# Gesamtschaltung.net
KiCad netlist of a schematic drawn in EAGLE
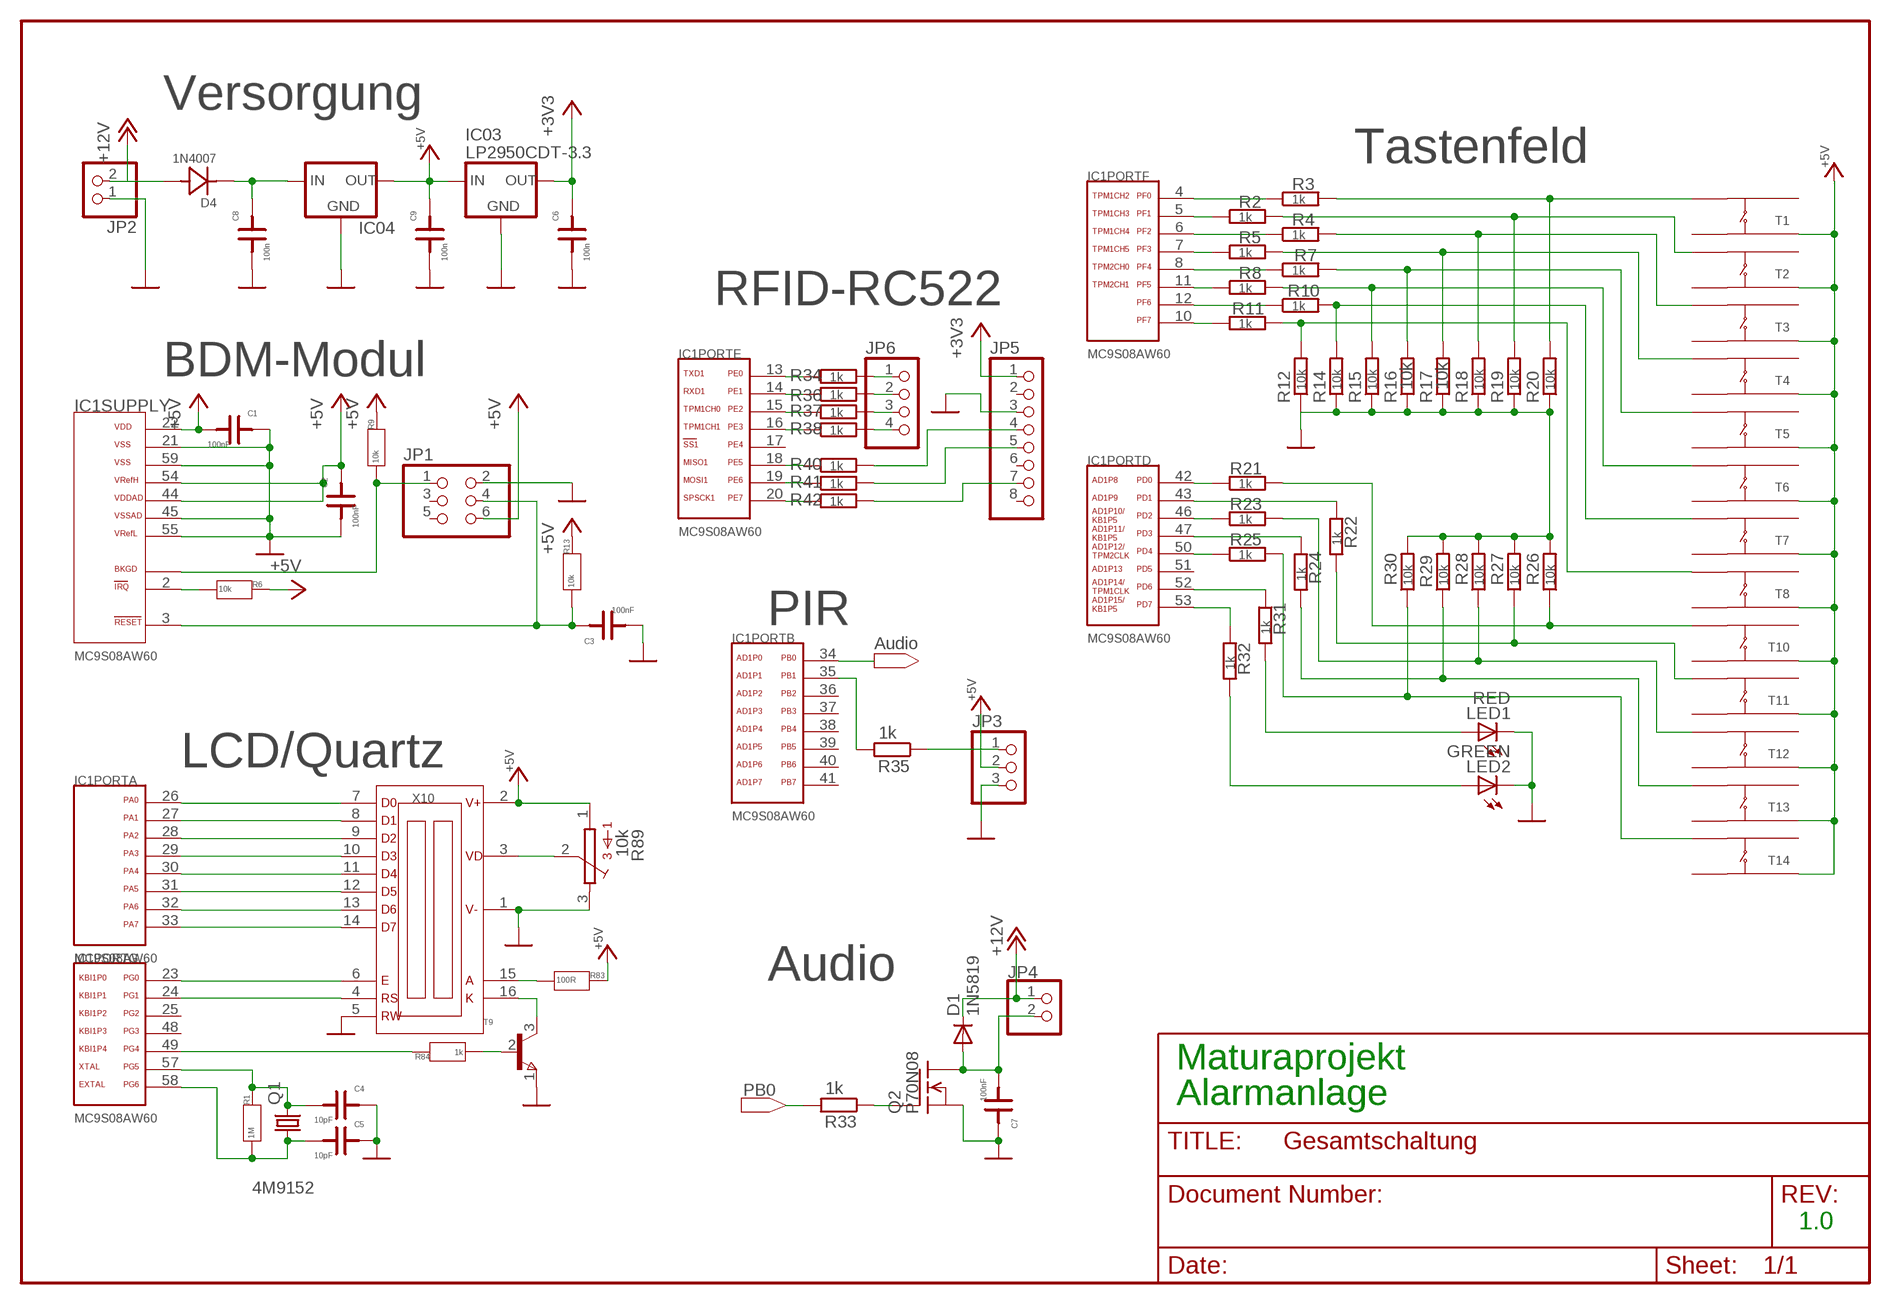
[diagram p0: schematic, sheet 1]

(export (version "E")
  (design (tool "Eeschema 10.0.6"))
  (components
    (comp (ref "C1")
      (value "100nF")
      (footprint "eagle-import:0805F")
      (libsource (lib "eagle-import") (part "C1"))
    )
    (comp (ref "C2")
      (value "100nF")
      (footprint "eagle-import:0805F")
      (libsource (lib "eagle-import") (part "C1"))
    )
    (comp (ref "C3")
      (value "100nF")
      (footprint "eagle-import:0805F")
      (libsource (lib "eagle-import") (part "C1"))
    )
    (comp (ref "C4")
      (value "10pF")
      (footprint "eagle-import:0805F")
      (libsource (lib "eagle-import") (part "C1"))
    )
    (comp (ref "C5")
      (value "10pF")
      (footprint "eagle-import:0805F")
      (libsource (lib "eagle-import") (part "C1"))
    )
    (comp (ref "C6")
      (value "100n")
      (footprint "eagle-import:0805F")
      (libsource (lib "eagle-import") (part "C1"))
    )
    (comp (ref "C7")
      (value "100nF")
      (footprint "eagle-import:0805F")
      (libsource (lib "eagle-import") (part "C1"))
    )
    (comp (ref "C8")
      (value "100n")
      (footprint "eagle-import:0805F")
      (libsource (lib "eagle-import") (part "C1"))
    )
    (comp (ref "C9")
      (value "100n")
      (footprint "eagle-import:0805F")
      (libsource (lib "eagle-import") (part "C1"))
    )
    (comp (ref "D1")
      (value "1N5819")
      (footprint "eagle-import:DO41-10")
      (libsource (lib "eagle-import") (part "1N4004"))
    )
    (comp (ref "D4")
      (value "1N4007")
      (footprint "eagle-import:D400BH")
      (libsource (lib "eagle-import") (part "DHC"))
    )
    (comp (ref "IC1")
      (value "MC9S08AW60")
      (footprint "eagle-import:LQFP64")
      (libsource (lib "eagle-import") (part "MC9S08AW60"))
    )
    (comp (ref "IC03")
      (value "LP2950CDT-3.3")
      (footprint "eagle-import:DPACK")
      (libsource (lib "eagle-import") (part "LP2950?CDT-3.3"))
    )
    (comp (ref "IC04")
      (value "78XXS")
      (footprint "eagle-import:78XXS")
      (libsource (lib "eagle-import") (part "78XXS"))
    )
    (comp (ref "JP1")
      (value "PINHD-2X3")
      (footprint "eagle-import:2X03")
      (libsource (lib "eagle-import") (part "PINHD-2X3"))
    )
    (comp (ref "JP2")
      (value "PINHD-1X2")
      (footprint "eagle-import:1X02")
      (libsource (lib "eagle-import") (part "PINHD-1X2"))
    )
    (comp (ref "JP3")
      (value "PINHD-1X3")
      (footprint "eagle-import:1X03")
      (libsource (lib "eagle-import") (part "PINHD-1X3"))
    )
    (comp (ref "JP4")
      (value "PINHD-1X2")
      (footprint "eagle-import:1X02")
      (libsource (lib "eagle-import") (part "PINHD-1X2"))
    )
    (comp (ref "JP5")
      (value "PINHD-1X8")
      (footprint "eagle-import:1X08")
      (libsource (lib "eagle-import") (part "PINHD-1X8"))
    )
    (comp (ref "JP6")
      (value "PINHD-1X4")
      (footprint "eagle-import:1X04")
      (libsource (lib "eagle-import") (part "PINHD-1X4"))
    )
    (comp (ref "LED1")
      (value "RED")
      (footprint "eagle-import:LED3MM")
      (libsource (lib "eagle-import") (part "LED3MM"))
    )
    (comp (ref "LED2")
      (value "GREEN")
      (footprint "eagle-import:LED3MM")
      (libsource (lib "eagle-import") (part "LED3MM"))
    )
    (comp (ref "Q1")
      (value "4M9152")
      (footprint "eagle-import:HC49UP")
      (libsource (lib "eagle-import") (part "HC49UP"))
    )
    (comp (ref "Q2")
      (value "P70N08")
      (footprint "eagle-import:TO220")
      (libsource (lib "eagle-import") (part "BUZ11"))
    )
    (comp (ref "R1")
      (value "1M")
      (footprint "eagle-import:0805")
      (libsource (lib "eagle-import") (part "R1"))
    )
    (comp (ref "R2")
      (value "1k")
      (footprint "eagle-import:M0805")
      (libsource (lib "eagle-import") (part "R-EU_M0805"))
    )
    (comp (ref "R3")
      (value "1k")
      (footprint "eagle-import:M0805")
      (libsource (lib "eagle-import") (part "R-EU_M0805"))
    )
    (comp (ref "R4")
      (value "1k")
      (footprint "eagle-import:M0805")
      (libsource (lib "eagle-import") (part "R-EU_M0805"))
    )
    (comp (ref "R5")
      (value "1k")
      (footprint "eagle-import:M0805")
      (libsource (lib "eagle-import") (part "R-EU_M0805"))
    )
    (comp (ref "R6")
      (value "10k")
      (footprint "eagle-import:0805")
      (libsource (lib "eagle-import") (part "R1"))
    )
    (comp (ref "R7")
      (value "1k")
      (footprint "eagle-import:M0805")
      (libsource (lib "eagle-import") (part "R-EU_M0805"))
    )
    (comp (ref "R8")
      (value "1k")
      (footprint "eagle-import:M0805")
      (libsource (lib "eagle-import") (part "R-EU_M0805"))
    )
    (comp (ref "R9")
      (value "10k")
      (footprint "eagle-import:0805")
      (libsource (lib "eagle-import") (part "R1"))
    )
    (comp (ref "R10")
      (value "1k")
      (footprint "eagle-import:M0805")
      (libsource (lib "eagle-import") (part "R-EU_M0805"))
    )
    (comp (ref "R11")
      (value "1k")
      (footprint "eagle-import:M0805")
      (libsource (lib "eagle-import") (part "R-EU_M0805"))
    )
    (comp (ref "R12")
      (value "10k")
      (footprint "eagle-import:M0805")
      (libsource (lib "eagle-import") (part "R-EU_M0805"))
    )
    (comp (ref "R13")
      (value "10k")
      (footprint "eagle-import:0805")
      (libsource (lib "eagle-import") (part "R1"))
    )
    (comp (ref "R14")
      (value "10k")
      (footprint "eagle-import:M0805")
      (libsource (lib "eagle-import") (part "R-EU_M0805"))
    )
    (comp (ref "R15")
      (value "10k")
      (footprint "eagle-import:M0805")
      (libsource (lib "eagle-import") (part "R-EU_M0805"))
    )
    (comp (ref "R16")
      (value "10k")
      (footprint "eagle-import:M0805")
      (libsource (lib "eagle-import") (part "R-EU_M0805"))
    )
    (comp (ref "R17")
      (value "10k")
      (footprint "eagle-import:M0805")
      (libsource (lib "eagle-import") (part "R-EU_M0805"))
    )
    (comp (ref "R18")
      (value "10k")
      (footprint "eagle-import:M0805")
      (libsource (lib "eagle-import") (part "R-EU_M0805"))
    )
    (comp (ref "R19")
      (value "10k")
      (footprint "eagle-import:M0805")
      (libsource (lib "eagle-import") (part "R-EU_M0805"))
    )
    (comp (ref "R20")
      (value "10k")
      (footprint "eagle-import:M0805")
      (libsource (lib "eagle-import") (part "R-EU_M0805"))
    )
    (comp (ref "R21")
      (value "1k")
      (footprint "eagle-import:M0805")
      (libsource (lib "eagle-import") (part "R-EU_M0805"))
    )
    (comp (ref "R22")
      (value "1k")
      (footprint "eagle-import:M0805")
      (libsource (lib "eagle-import") (part "R-EU_M0805"))
    )
    (comp (ref "R23")
      (value "1k")
      (footprint "eagle-import:M0805")
      (libsource (lib "eagle-import") (part "R-EU_M0805"))
    )
    (comp (ref "R24")
      (value "1k")
      (footprint "eagle-import:M0805")
      (libsource (lib "eagle-import") (part "R-EU_M0805"))
    )
    (comp (ref "R25")
      (value "1k")
      (footprint "eagle-import:M0805")
      (libsource (lib "eagle-import") (part "R-EU_M0805"))
    )
    (comp (ref "R26")
      (value "10k")
      (footprint "eagle-import:M0805")
      (libsource (lib "eagle-import") (part "R-EU_M0805"))
    )
    (comp (ref "R27")
      (value "10k")
      (footprint "eagle-import:M0805")
      (libsource (lib "eagle-import") (part "R-EU_M0805"))
    )
    (comp (ref "R28")
      (value "10k")
      (footprint "eagle-import:M0805")
      (libsource (lib "eagle-import") (part "R-EU_M0805"))
    )
    (comp (ref "R29")
      (value "10k")
      (footprint "eagle-import:M0805")
      (libsource (lib "eagle-import") (part "R-EU_M0805"))
    )
    (comp (ref "R30")
      (value "10k")
      (footprint "eagle-import:M0805")
      (libsource (lib "eagle-import") (part "R-EU_M0805"))
    )
    (comp (ref "R31")
      (value "1k")
      (footprint "eagle-import:R0805")
      (libsource (lib "eagle-import") (part "R-EU_R0805"))
    )
    (comp (ref "R32")
      (value "1k")
      (footprint "eagle-import:R0805")
      (libsource (lib "eagle-import") (part "R-EU_R0805"))
    )
    (comp (ref "R33")
      (value "1k")
      (footprint "eagle-import:0207_10")
      (libsource (lib "eagle-import") (part "R-EU_0207/10"))
    )
    (comp (ref "R34")
      (value "1k")
      (footprint "eagle-import:M0805")
      (libsource (lib "eagle-import") (part "R-EU_M0805"))
    )
    (comp (ref "R35")
      (value "1k")
      (footprint "eagle-import:M0805")
      (libsource (lib "eagle-import") (part "R-EU_M0805"))
    )
    (comp (ref "R36")
      (value "1k")
      (footprint "eagle-import:M0805")
      (libsource (lib "eagle-import") (part "R-EU_M0805"))
    )
    (comp (ref "R37")
      (value "1k")
      (footprint "eagle-import:M0805")
      (libsource (lib "eagle-import") (part "R-EU_M0805"))
    )
    (comp (ref "R38")
      (value "1k")
      (footprint "eagle-import:M0805")
      (libsource (lib "eagle-import") (part "R-EU_M0805"))
    )
    (comp (ref "R40")
      (value "1k")
      (footprint "eagle-import:M0805")
      (libsource (lib "eagle-import") (part "R-EU_M0805"))
    )
    (comp (ref "R41")
      (value "1k")
      (footprint "eagle-import:M0805")
      (libsource (lib "eagle-import") (part "R-EU_M0805"))
    )
    (comp (ref "R42")
      (value "1k")
      (footprint "eagle-import:M0805")
      (libsource (lib "eagle-import") (part "R-EU_M0805"))
    )
    (comp (ref "R83")
      (value "100R")
      (footprint "eagle-import:0805")
      (libsource (lib "eagle-import") (part "R1"))
    )
    (comp (ref "R84")
      (value "1k")
      (footprint "eagle-import:0805")
      (libsource (lib "eagle-import") (part "R1"))
    )
    (comp (ref "R89")
      (value "10k")
      (footprint "eagle-import:S63X")
      (libsource (lib "eagle-import") (part "S63X"))
    )
    (comp (ref "T1")
      (value "TASTERTHT")
      (footprint "eagle-import:TASTE_THT")
      (libsource (lib "eagle-import") (part "TASTERTHT"))
    )
    (comp (ref "T2")
      (value "TASTERTHT")
      (footprint "eagle-import:TASTE_THT")
      (libsource (lib "eagle-import") (part "TASTERTHT"))
    )
    (comp (ref "T3")
      (value "TASTERTHT")
      (footprint "eagle-import:TASTE_THT")
      (libsource (lib "eagle-import") (part "TASTERTHT"))
    )
    (comp (ref "T4")
      (value "TASTERTHT")
      (footprint "eagle-import:TASTE_THT")
      (libsource (lib "eagle-import") (part "TASTERTHT"))
    )
    (comp (ref "T5")
      (value "TASTERTHT")
      (footprint "eagle-import:TASTE_THT")
      (libsource (lib "eagle-import") (part "TASTERTHT"))
    )
    (comp (ref "T6")
      (value "TASTERTHT")
      (footprint "eagle-import:TASTE_THT")
      (libsource (lib "eagle-import") (part "TASTERTHT"))
    )
    (comp (ref "T7")
      (value "TASTERTHT")
      (footprint "eagle-import:TASTE_THT")
      (libsource (lib "eagle-import") (part "TASTERTHT"))
    )
    (comp (ref "T8")
      (value "TASTERTHT")
      (footprint "eagle-import:TASTE_THT")
      (libsource (lib "eagle-import") (part "TASTERTHT"))
    )
    (comp (ref "T9")
      (value "BC817")
      (footprint "eagle-import:SOT-23")
      (libsource (lib "eagle-import") (part "BC817"))
    )
    (comp (ref "T10")
      (value "TASTERTHT")
      (footprint "eagle-import:TASTE_THT")
      (libsource (lib "eagle-import") (part "TASTERTHT"))
    )
    (comp (ref "T11")
      (value "TASTERTHT")
      (footprint "eagle-import:TASTE_THT")
      (libsource (lib "eagle-import") (part "TASTERTHT"))
    )
    (comp (ref "T12")
      (value "TASTERTHT")
      (footprint "eagle-import:TASTE_THT")
      (libsource (lib "eagle-import") (part "TASTERTHT"))
    )
    (comp (ref "T13")
      (value "TASTERTHT")
      (footprint "eagle-import:TASTE_THT")
      (libsource (lib "eagle-import") (part "TASTERTHT"))
    )
    (comp (ref "T14")
      (value "TASTERTHT")
      (footprint "eagle-import:TASTE_THT")
      (libsource (lib "eagle-import") (part "TASTERTHT"))
    )
    (comp (ref "X10")
      (value "FDCC1602E")
      (footprint "eagle-import:FDCC1602E")
      (libsource (lib "eagle-import") (part "FDCC1602E"))
    )
  )
  (nets
    (net (code "1") (name "+3V3") (class "Default")
      (node (ref "C6") (pin "2") (pinfunction "2_2") (pintype "bidirectional"))
      (node (ref "IC03") (pin "3") (pinfunction "OUT_3") (pintype "passive"))
      (node (ref "JP5") (pin "1") (pinfunction "1_1") (pintype "passive"))
    )
    (net (code "2") (name "+5V") (class "Default")
      (node (ref "C1") (pin "1") (pinfunction "1_1") (pintype "bidirectional"))
      (node (ref "C2") (pin "2") (pinfunction "2_2") (pintype "bidirectional"))
      (node (ref "C9") (pin "2") (pinfunction "2_2") (pintype "bidirectional"))
      (node (ref "IC03") (pin "1") (pinfunction "IN_1") (pintype "input"))
      (node (ref "IC04") (pin "OUT") (pinfunction "OUT_OUT") (pintype "passive"))
      (node (ref "IC1") (pin "22") (pinfunction "VDD_22") (pintype "bidirectional"))
      (node (ref "IC1") (pin "44") (pinfunction "VDDAD_44") (pintype "bidirectional"))
      (node (ref "IC1") (pin "54") (pinfunction "VREFH_54") (pintype "bidirectional"))
      (node (ref "JP1") (pin "6") (pinfunction "6_6") (pintype "passive"))
      (node (ref "JP3") (pin "2") (pinfunction "2_2") (pintype "passive"))
      (node (ref "R13") (pin "2") (pinfunction "2_2") (pintype "bidirectional"))
      (node (ref "R6") (pin "2") (pinfunction "2_2") (pintype "bidirectional"))
      (node (ref "R83") (pin "2") (pinfunction "2_2") (pintype "bidirectional"))
      (node (ref "R89") (pin "1") (pinfunction "1_1") (pintype "passive"))
      (node (ref "R9") (pin "2") (pinfunction "2_2") (pintype "bidirectional"))
      (node (ref "T1") (pin "A1") (pinfunction "A1_A1") (pintype "bidirectional"))
      (node (ref "T10") (pin "A1") (pinfunction "A1_A1") (pintype "bidirectional"))
      (node (ref "T11") (pin "A1") (pinfunction "A1_A1") (pintype "bidirectional"))
      (node (ref "T12") (pin "A1") (pinfunction "A1_A1") (pintype "bidirectional"))
      (node (ref "T13") (pin "A1") (pinfunction "A1_A1") (pintype "bidirectional"))
      (node (ref "T14") (pin "A1") (pinfunction "A1_A1") (pintype "bidirectional"))
      (node (ref "T2") (pin "A1") (pinfunction "A1_A1") (pintype "bidirectional"))
      (node (ref "T3") (pin "A1") (pinfunction "A1_A1") (pintype "bidirectional"))
      (node (ref "T4") (pin "A1") (pinfunction "A1_A1") (pintype "bidirectional"))
      (node (ref "T5") (pin "A1") (pinfunction "A1_A1") (pintype "bidirectional"))
      (node (ref "T6") (pin "A1") (pinfunction "A1_A1") (pintype "bidirectional"))
      (node (ref "T7") (pin "A1") (pinfunction "A1_A1") (pintype "bidirectional"))
      (node (ref "T8") (pin "A1") (pinfunction "A1_A1") (pintype "bidirectional"))
      (node (ref "X10") (pin "2") (pinfunction "V+_2") (pintype "bidirectional"))
    )
    (net (code "3") (name "+12V") (class "Default")
      (node (ref "D1") (pin "C") (pinfunction "C_C") (pintype "passive"))
      (node (ref "D4") (pin "A") (pinfunction "A_A") (pintype "bidirectional"))
      (node (ref "JP2") (pin "2") (pinfunction "2_2") (pintype "passive"))
      (node (ref "JP4") (pin "1") (pinfunction "1_1") (pintype "passive"))
    )
    (net (code "4") (name "/N$36") (class "Default")
      (node (ref "IC1") (pin "34") (pinfunction "PB0_34") (pintype "bidirectional"))
      (node (ref "R33") (pin "2") (pinfunction "2_2") (pintype "passive"))
    )
    (net (code "5") (name "GND") (class "Default")
      (node (ref "C1") (pin "2") (pinfunction "2_2") (pintype "bidirectional"))
      (node (ref "C2") (pin "1") (pinfunction "1_1") (pintype "bidirectional"))
      (node (ref "C3") (pin "1") (pinfunction "1_1") (pintype "bidirectional"))
      (node (ref "C4") (pin "2") (pinfunction "2_2") (pintype "bidirectional"))
      (node (ref "C5") (pin "2") (pinfunction "2_2") (pintype "bidirectional"))
      (node (ref "C6") (pin "1") (pinfunction "1_1") (pintype "bidirectional"))
      (node (ref "C7") (pin "2") (pinfunction "2_2") (pintype "bidirectional"))
      (node (ref "C8") (pin "1") (pinfunction "1_1") (pintype "bidirectional"))
      (node (ref "C9") (pin "1") (pinfunction "1_1") (pintype "bidirectional"))
      (node (ref "IC03") (pin "4") (pinfunction "GND_4") (pintype "input"))
      (node (ref "IC04") (pin "GND") (pinfunction "GND_GND") (pintype "input"))
      (node (ref "IC1") (pin "21") (pinfunction "VSS_21") (pintype "bidirectional"))
      (node (ref "IC1") (pin "45") (pinfunction "VSSAD_45") (pintype "bidirectional"))
      (node (ref "IC1") (pin "55") (pinfunction "VREFL_55") (pintype "bidirectional"))
      (node (ref "IC1") (pin "59") (pinfunction "VSS2_59") (pintype "bidirectional"))
      (node (ref "JP1") (pin "2") (pinfunction "2_2") (pintype "passive"))
      (node (ref "JP2") (pin "1") (pinfunction "1_1") (pintype "passive"))
      (node (ref "JP3") (pin "3") (pinfunction "3_3") (pintype "passive"))
      (node (ref "JP5") (pin "3") (pinfunction "3_3") (pintype "passive"))
      (node (ref "LED1") (pin "K") (pinfunction "C_K") (pintype "passive"))
      (node (ref "LED2") (pin "K") (pinfunction "C_K") (pintype "passive"))
      (node (ref "Q2") (pin "3") (pinfunction "S_3") (pintype "passive"))
      (node (ref "R12") (pin "1") (pinfunction "1_1") (pintype "passive"))
      (node (ref "R14") (pin "1") (pinfunction "1_1") (pintype "passive"))
      (node (ref "R15") (pin "1") (pinfunction "1_1") (pintype "passive"))
      (node (ref "R16") (pin "1") (pinfunction "1_1") (pintype "passive"))
      (node (ref "R17") (pin "1") (pinfunction "1_1") (pintype "passive"))
      (node (ref "R18") (pin "1") (pinfunction "1_1") (pintype "passive"))
      (node (ref "R19") (pin "1") (pinfunction "1_1") (pintype "passive"))
      (node (ref "R20") (pin "1") (pinfunction "1_1") (pintype "passive"))
      (node (ref "R26") (pin "2") (pinfunction "2_2") (pintype "passive"))
      (node (ref "R27") (pin "2") (pinfunction "2_2") (pintype "passive"))
      (node (ref "R28") (pin "2") (pinfunction "2_2") (pintype "passive"))
      (node (ref "R29") (pin "2") (pinfunction "2_2") (pintype "passive"))
      (node (ref "R30") (pin "2") (pinfunction "2_2") (pintype "passive"))
      (node (ref "R89") (pin "3") (pinfunction "3_3") (pintype "passive"))
      (node (ref "T9") (pin "1") (pinfunction "E_1") (pintype "passive"))
      (node (ref "X10") (pin "1") (pinfunction "V-_1") (pintype "bidirectional"))
      (node (ref "X10") (pin "5") (pinfunction "RW_5") (pintype "bidirectional"))
    )
    (net (code "6") (name "Net-(C8-Pad2)") (class "Default")
      (node (ref "C8") (pin "2") (pinfunction "2_2") (pintype "bidirectional"))
      (node (ref "D4") (pin "K") (pinfunction "K_K") (pintype "bidirectional"))
      (node (ref "IC04") (pin "IN") (pinfunction "IN_IN") (pintype "input"))
    )
    (net (code "7") (name "Net-(IC1A-PA0)") (class "Default")
      (node (ref "IC1") (pin "26") (pinfunction "PA0_26") (pintype "bidirectional"))
      (node (ref "X10") (pin "7") (pinfunction "D0_7") (pintype "bidirectional"))
    )
    (net (code "8") (name "Net-(IC1A-PA1)") (class "Default")
      (node (ref "IC1") (pin "27") (pinfunction "PA1_27") (pintype "bidirectional"))
      (node (ref "X10") (pin "8") (pinfunction "D1_8") (pintype "bidirectional"))
    )
    (net (code "9") (name "Net-(IC1A-PA2)") (class "Default")
      (node (ref "IC1") (pin "28") (pinfunction "PA2_28") (pintype "bidirectional"))
      (node (ref "X10") (pin "9") (pinfunction "D2_9") (pintype "bidirectional"))
    )
    (net (code "10") (name "Net-(IC1A-PA3)") (class "Default")
      (node (ref "IC1") (pin "29") (pinfunction "PA3_29") (pintype "bidirectional"))
      (node (ref "X10") (pin "10") (pinfunction "D3_10") (pintype "bidirectional"))
    )
    (net (code "11") (name "Net-(IC1A-PA4)") (class "Default")
      (node (ref "IC1") (pin "30") (pinfunction "PA4_30") (pintype "bidirectional"))
      (node (ref "X10") (pin "11") (pinfunction "D4_11") (pintype "bidirectional"))
    )
    (net (code "12") (name "Net-(IC1A-PA5)") (class "Default")
      (node (ref "IC1") (pin "31") (pinfunction "PA5_31") (pintype "bidirectional"))
      (node (ref "X10") (pin "12") (pinfunction "D5_12") (pintype "bidirectional"))
    )
    (net (code "13") (name "Net-(IC1A-PA6)") (class "Default")
      (node (ref "IC1") (pin "32") (pinfunction "PA6_32") (pintype "bidirectional"))
      (node (ref "X10") (pin "13") (pinfunction "D6_13") (pintype "bidirectional"))
    )
    (net (code "14") (name "Net-(IC1A-PA7)") (class "Default")
      (node (ref "IC1") (pin "33") (pinfunction "PA7_33") (pintype "bidirectional"))
      (node (ref "X10") (pin "14") (pinfunction "D7_14") (pintype "bidirectional"))
    )
    (net (code "15") (name "Net-(IC1B-PB1)") (class "Default")
      (node (ref "IC1") (pin "35") (pinfunction "PB1_35") (pintype "bidirectional"))
      (node (ref "R35") (pin "2") (pinfunction "2_2") (pintype "passive"))
    )
    (net (code "16") (name "Net-(IC1D-PD0)") (class "Default")
      (node (ref "IC1") (pin "42") (pinfunction "PD0_42") (pintype "bidirectional"))
      (node (ref "R21") (pin "1") (pinfunction "1_1") (pintype "passive"))
    )
    (net (code "17") (name "Net-(IC1D-PD1)") (class "Default")
      (node (ref "IC1") (pin "43") (pinfunction "PD1_43") (pintype "bidirectional"))
      (node (ref "R22") (pin "1") (pinfunction "1_1") (pintype "passive"))
    )
    (net (code "18") (name "Net-(IC1D-PD2)") (class "Default")
      (node (ref "IC1") (pin "46") (pinfunction "PD2_46") (pintype "bidirectional"))
      (node (ref "R23") (pin "1") (pinfunction "1_1") (pintype "passive"))
    )
    (net (code "19") (name "Net-(IC1D-PD3)") (class "Default")
      (node (ref "IC1") (pin "47") (pinfunction "PD3_47") (pintype "bidirectional"))
      (node (ref "R24") (pin "1") (pinfunction "1_1") (pintype "passive"))
    )
    (net (code "20") (name "Net-(IC1D-PD4)") (class "Default")
      (node (ref "IC1") (pin "50") (pinfunction "PD4_50") (pintype "bidirectional"))
      (node (ref "R25") (pin "1") (pinfunction "1_1") (pintype "passive"))
    )
    (net (code "21") (name "Net-(IC1D-PD6)") (class "Default")
      (node (ref "IC1") (pin "52") (pinfunction "PD6_52") (pintype "bidirectional"))
      (node (ref "R31") (pin "1") (pinfunction "1_1") (pintype "passive"))
    )
    (net (code "22") (name "Net-(IC1D-PD7)") (class "Default")
      (node (ref "IC1") (pin "53") (pinfunction "PD7_53") (pintype "bidirectional"))
      (node (ref "R32") (pin "1") (pinfunction "1_1") (pintype "passive"))
    )
    (net (code "23") (name "Net-(IC1E-PE0)") (class "Default")
      (node (ref "IC1") (pin "13") (pinfunction "PE0_13") (pintype "bidirectional"))
      (node (ref "R34") (pin "1") (pinfunction "1_1") (pintype "passive"))
    )
    (net (code "24") (name "Net-(IC1E-PE1)") (class "Default")
      (node (ref "IC1") (pin "14") (pinfunction "PE1_14") (pintype "bidirectional"))
      (node (ref "R36") (pin "1") (pinfunction "1_1") (pintype "passive"))
    )
    (net (code "25") (name "Net-(IC1E-PE2)") (class "Default")
      (node (ref "IC1") (pin "15") (pinfunction "PE2_15") (pintype "bidirectional"))
      (node (ref "R37") (pin "1") (pinfunction "1_1") (pintype "passive"))
    )
    (net (code "26") (name "Net-(IC1E-PE3)") (class "Default")
      (node (ref "IC1") (pin "16") (pinfunction "PE3_16") (pintype "bidirectional"))
      (node (ref "R38") (pin "1") (pinfunction "1_1") (pintype "passive"))
    )
    (net (code "27") (name "Net-(IC1E-PE5)") (class "Default")
      (node (ref "IC1") (pin "18") (pinfunction "PE5_18") (pintype "bidirectional"))
      (node (ref "R40") (pin "1") (pinfunction "1_1") (pintype "passive"))
    )
    (net (code "28") (name "Net-(IC1E-PE6)") (class "Default")
      (node (ref "IC1") (pin "19") (pinfunction "PE6_19") (pintype "bidirectional"))
      (node (ref "R41") (pin "1") (pinfunction "1_1") (pintype "passive"))
    )
    (net (code "29") (name "Net-(IC1E-PE7)") (class "Default")
      (node (ref "IC1") (pin "20") (pinfunction "PE7_20") (pintype "bidirectional"))
      (node (ref "R42") (pin "1") (pinfunction "1_1") (pintype "passive"))
    )
    (net (code "30") (name "Net-(IC1F-PF0)") (class "Default")
      (node (ref "IC1") (pin "4") (pinfunction "PF0_4") (pintype "bidirectional"))
      (node (ref "R3") (pin "1") (pinfunction "1_1") (pintype "passive"))
    )
    (net (code "31") (name "Net-(IC1F-PF1)") (class "Default")
      (node (ref "IC1") (pin "5") (pinfunction "PF1_5") (pintype "bidirectional"))
      (node (ref "R2") (pin "1") (pinfunction "1_1") (pintype "passive"))
    )
    (net (code "32") (name "Net-(IC1F-PF2)") (class "Default")
      (node (ref "IC1") (pin "6") (pinfunction "PF2_6") (pintype "bidirectional"))
      (node (ref "R4") (pin "1") (pinfunction "1_1") (pintype "passive"))
    )
    (net (code "33") (name "Net-(IC1F-PF3)") (class "Default")
      (node (ref "IC1") (pin "7") (pinfunction "PF3_7") (pintype "bidirectional"))
      (node (ref "R5") (pin "1") (pinfunction "1_1") (pintype "passive"))
    )
    (net (code "34") (name "Net-(IC1F-PF4)") (class "Default")
      (node (ref "IC1") (pin "8") (pinfunction "PF4_8") (pintype "bidirectional"))
      (node (ref "R7") (pin "1") (pinfunction "1_1") (pintype "passive"))
    )
    (net (code "35") (name "Net-(IC1F-PF5)") (class "Default")
      (node (ref "IC1") (pin "11") (pinfunction "PF5_11") (pintype "bidirectional"))
      (node (ref "R8") (pin "1") (pinfunction "1_1") (pintype "passive"))
    )
    (net (code "36") (name "Net-(IC1F-PF6)") (class "Default")
      (node (ref "IC1") (pin "12") (pinfunction "PF6_12") (pintype "bidirectional"))
      (node (ref "R10") (pin "1") (pinfunction "1_1") (pintype "passive"))
    )
    (net (code "37") (name "Net-(IC1F-PF7)") (class "Default")
      (node (ref "IC1") (pin "10") (pinfunction "PF7_10") (pintype "bidirectional"))
      (node (ref "R11") (pin "1") (pinfunction "1_1") (pintype "passive"))
    )
    (net (code "38") (name "Net-(IC1G-PG0)") (class "Default")
      (node (ref "IC1") (pin "23") (pinfunction "PG0_23") (pintype "bidirectional"))
      (node (ref "X10") (pin "6") (pinfunction "E_6") (pintype "bidirectional"))
    )
    (net (code "39") (name "Net-(IC1G-PG1)") (class "Default")
      (node (ref "IC1") (pin "24") (pinfunction "PG1_24") (pintype "bidirectional"))
      (node (ref "X10") (pin "4") (pinfunction "RS_4") (pintype "bidirectional"))
    )
    (net (code "40") (name "Net-(IC1G-PG4)") (class "Default")
      (node (ref "IC1") (pin "49") (pinfunction "PG4_49") (pintype "bidirectional"))
      (node (ref "R84") (pin "2") (pinfunction "2_2") (pintype "bidirectional"))
    )
    (net (code "41") (name "Net-(IC1G-PG5)") (class "Default")
      (node (ref "C4") (pin "1") (pinfunction "1_1") (pintype "bidirectional"))
      (node (ref "IC1") (pin "57") (pinfunction "PG5_57") (pintype "bidirectional"))
      (node (ref "Q1") (pin "2") (pinfunction "2_2") (pintype "passive"))
      (node (ref "R1") (pin "2") (pinfunction "2_2") (pintype "bidirectional"))
    )
    (net (code "42") (name "Net-(IC1G-PG6)") (class "Default")
      (node (ref "C5") (pin "1") (pinfunction "1_1") (pintype "bidirectional"))
      (node (ref "IC1") (pin "58") (pinfunction "PG6_58") (pintype "bidirectional"))
      (node (ref "Q1") (pin "1") (pinfunction "1_1") (pintype "passive"))
      (node (ref "R1") (pin "1") (pinfunction "1_1") (pintype "bidirectional"))
    )
    (net (code "43") (name "Net-(IC1H-BKGD)") (class "Default")
      (node (ref "IC1") (pin "56") (pinfunction "BKGD_56") (pintype "bidirectional"))
      (node (ref "JP1") (pin "1") (pinfunction "1_1") (pintype "passive"))
      (node (ref "R9") (pin "1") (pinfunction "1_1") (pintype "bidirectional"))
    )
    (net (code "44") (name "Net-(IC1H-IRQ{slash})") (class "Default")
      (node (ref "IC1") (pin "2") (pinfunction "IRQ/_2") (pintype "bidirectional"))
      (node (ref "R6") (pin "1") (pinfunction "1_1") (pintype "bidirectional"))
    )
    (net (code "45") (name "Net-(IC1H-RST{slash})") (class "Default")
      (node (ref "C3") (pin "2") (pinfunction "2_2") (pintype "bidirectional"))
      (node (ref "IC1") (pin "3") (pinfunction "RST/_3") (pintype "bidirectional"))
      (node (ref "JP1") (pin "4") (pinfunction "4_4") (pintype "passive"))
      (node (ref "R13") (pin "1") (pinfunction "1_1") (pintype "bidirectional"))
    )
    (net (code "46") (name "Net-(JP3-Pad1)") (class "Default")
      (node (ref "JP3") (pin "1") (pinfunction "1_1") (pintype "passive"))
      (node (ref "R35") (pin "1") (pinfunction "1_1") (pintype "passive"))
    )
    (net (code "47") (name "Net-(JP5-Pad4)") (class "Default")
      (node (ref "JP5") (pin "4") (pinfunction "4_4") (pintype "passive"))
      (node (ref "R40") (pin "2") (pinfunction "2_2") (pintype "passive"))
    )
    (net (code "48") (name "Net-(JP5-Pad5)") (class "Default")
      (node (ref "JP5") (pin "5") (pinfunction "5_5") (pintype "passive"))
      (node (ref "R41") (pin "2") (pinfunction "2_2") (pintype "passive"))
    )
    (net (code "49") (name "Net-(JP5-Pad7)") (class "Default")
      (node (ref "JP5") (pin "7") (pinfunction "7_7") (pintype "passive"))
      (node (ref "R42") (pin "2") (pinfunction "2_2") (pintype "passive"))
    )
    (net (code "50") (name "Net-(JP6-Pad1)") (class "Default")
      (node (ref "JP6") (pin "1") (pinfunction "1_1") (pintype "passive"))
      (node (ref "R34") (pin "2") (pinfunction "2_2") (pintype "passive"))
    )
    (net (code "51") (name "Net-(JP6-Pad2)") (class "Default")
      (node (ref "JP6") (pin "2") (pinfunction "2_2") (pintype "passive"))
      (node (ref "R36") (pin "2") (pinfunction "2_2") (pintype "passive"))
    )
    (net (code "52") (name "Net-(JP6-Pad3)") (class "Default")
      (node (ref "JP6") (pin "3") (pinfunction "3_3") (pintype "passive"))
      (node (ref "R37") (pin "2") (pinfunction "2_2") (pintype "passive"))
    )
    (net (code "53") (name "Net-(JP6-Pad4)") (class "Default")
      (node (ref "JP6") (pin "4") (pinfunction "4_4") (pintype "passive"))
      (node (ref "R38") (pin "2") (pinfunction "2_2") (pintype "passive"))
    )
    (net (code "54") (name "Net-(LED1-PadA)") (class "Default")
      (node (ref "LED1") (pin "A") (pinfunction "A_A") (pintype "passive"))
      (node (ref "R31") (pin "2") (pinfunction "2_2") (pintype "passive"))
    )
    (net (code "55") (name "Net-(LED2-PadA)") (class "Default")
      (node (ref "LED2") (pin "A") (pinfunction "A_A") (pintype "passive"))
      (node (ref "R32") (pin "2") (pinfunction "2_2") (pintype "passive"))
    )
    (net (code "56") (name "Net-(Q2-D)") (class "Default")
      (node (ref "C7") (pin "1") (pinfunction "1_1") (pintype "bidirectional"))
      (node (ref "D1") (pin "A") (pinfunction "A_A") (pintype "passive"))
      (node (ref "JP4") (pin "2") (pinfunction "2_2") (pintype "passive"))
      (node (ref "Q2") (pin "2") (pinfunction "D_2") (pintype "passive"))
    )
    (net (code "57") (name "Net-(Q2-G)") (class "Default")
      (node (ref "Q2") (pin "1") (pinfunction "G_1") (pintype "passive"))
      (node (ref "R33") (pin "1") (pinfunction "1_1") (pintype "passive"))
    )
    (net (code "58") (name "Net-(R10-Pad2)") (class "Default")
      (node (ref "R10") (pin "2") (pinfunction "2_2") (pintype "passive"))
      (node (ref "R14") (pin "2") (pinfunction "2_2") (pintype "passive"))
      (node (ref "T7") (pin "B2") (pinfunction "B2_B2") (pintype "bidirectional"))
    )
    (net (code "59") (name "Net-(R11-Pad2)") (class "Default")
      (node (ref "R11") (pin "2") (pinfunction "2_2") (pintype "passive"))
      (node (ref "R12") (pin "2") (pinfunction "2_2") (pintype "passive"))
      (node (ref "T8") (pin "B2") (pinfunction "B2_B2") (pintype "bidirectional"))
    )
    (net (code "60") (name "Net-(R15-Pad2)") (class "Default")
      (node (ref "R15") (pin "2") (pinfunction "2_2") (pintype "passive"))
      (node (ref "R8") (pin "2") (pinfunction "2_2") (pintype "passive"))
      (node (ref "T6") (pin "B2") (pinfunction "B2_B2") (pintype "bidirectional"))
    )
    (net (code "61") (name "Net-(R16-Pad2)") (class "Default")
      (node (ref "R16") (pin "2") (pinfunction "2_2") (pintype "passive"))
      (node (ref "R7") (pin "2") (pinfunction "2_2") (pintype "passive"))
      (node (ref "T5") (pin "B2") (pinfunction "B2_B2") (pintype "bidirectional"))
    )
    (net (code "62") (name "Net-(R17-Pad2)") (class "Default")
      (node (ref "R17") (pin "2") (pinfunction "2_2") (pintype "passive"))
      (node (ref "R5") (pin "2") (pinfunction "2_2") (pintype "passive"))
      (node (ref "T4") (pin "B2") (pinfunction "B2_B2") (pintype "bidirectional"))
    )
    (net (code "63") (name "Net-(R18-Pad2)") (class "Default")
      (node (ref "R18") (pin "2") (pinfunction "2_2") (pintype "passive"))
      (node (ref "R4") (pin "2") (pinfunction "2_2") (pintype "passive"))
      (node (ref "T3") (pin "B2") (pinfunction "B2_B2") (pintype "bidirectional"))
    )
    (net (code "64") (name "Net-(R19-Pad2)") (class "Default")
      (node (ref "R19") (pin "2") (pinfunction "2_2") (pintype "passive"))
      (node (ref "R2") (pin "2") (pinfunction "2_2") (pintype "passive"))
      (node (ref "T2") (pin "B2") (pinfunction "B2_B2") (pintype "bidirectional"))
    )
    (net (code "65") (name "Net-(R20-Pad2)") (class "Default")
      (node (ref "R20") (pin "2") (pinfunction "2_2") (pintype "passive"))
      (node (ref "R3") (pin "2") (pinfunction "2_2") (pintype "passive"))
      (node (ref "T1") (pin "B2") (pinfunction "B2_B2") (pintype "bidirectional"))
    )
    (net (code "66") (name "Net-(R21-Pad2)") (class "Default")
      (node (ref "R21") (pin "2") (pinfunction "2_2") (pintype "passive"))
      (node (ref "R26") (pin "1") (pinfunction "1_1") (pintype "passive"))
      (node (ref "T10") (pin "B2") (pinfunction "B2_B2") (pintype "bidirectional"))
    )
    (net (code "67") (name "Net-(R22-Pad2)") (class "Default")
      (node (ref "R22") (pin "2") (pinfunction "2_2") (pintype "passive"))
      (node (ref "R27") (pin "1") (pinfunction "1_1") (pintype "passive"))
      (node (ref "T11") (pin "B2") (pinfunction "B2_B2") (pintype "bidirectional"))
    )
    (net (code "68") (name "Net-(R23-Pad2)") (class "Default")
      (node (ref "R23") (pin "2") (pinfunction "2_2") (pintype "passive"))
      (node (ref "R28") (pin "1") (pinfunction "1_1") (pintype "passive"))
      (node (ref "T12") (pin "B2") (pinfunction "B2_B2") (pintype "bidirectional"))
    )
    (net (code "69") (name "Net-(R24-Pad2)") (class "Default")
      (node (ref "R24") (pin "2") (pinfunction "2_2") (pintype "passive"))
      (node (ref "R29") (pin "1") (pinfunction "1_1") (pintype "passive"))
      (node (ref "T13") (pin "B2") (pinfunction "B2_B2") (pintype "bidirectional"))
    )
    (net (code "70") (name "Net-(R25-Pad2)") (class "Default")
      (node (ref "R25") (pin "2") (pinfunction "2_2") (pintype "passive"))
      (node (ref "R30") (pin "1") (pinfunction "1_1") (pintype "passive"))
      (node (ref "T14") (pin "B2") (pinfunction "B2_B2") (pintype "bidirectional"))
    )
    (net (code "71") (name "Net-(T9-B)") (class "Default")
      (node (ref "R84") (pin "1") (pinfunction "1_1") (pintype "bidirectional"))
      (node (ref "T9") (pin "2") (pinfunction "B_2") (pintype "passive"))
    )
    (net (code "72") (name "Net-(T9-C)") (class "Default")
      (node (ref "T9") (pin "3") (pinfunction "C_3") (pintype "passive"))
      (node (ref "X10") (pin "16") (pinfunction "K_16") (pintype "bidirectional"))
    )
    (net (code "73") (name "Net-(X10-A)") (class "Default")
      (node (ref "R83") (pin "1") (pinfunction "1_1") (pintype "bidirectional"))
      (node (ref "X10") (pin "15") (pinfunction "A_15") (pintype "bidirectional"))
    )
    (net (code "74") (name "Net-(X10-VD)") (class "Default")
      (node (ref "R89") (pin "2") (pinfunction "2_2") (pintype "passive"))
      (node (ref "X10") (pin "3") (pinfunction "VD_3") (pintype "bidirectional"))
    )
    (net (code "75") (name "unconnected-(IC1B-PB2-Pad36)") (class "Default")
      (node (ref "IC1") (pin "36") (pinfunction "PB2_36") (pintype "bidirectional"))
    )
    (net (code "76") (name "unconnected-(IC1B-PB3-Pad37)") (class "Default")
      (node (ref "IC1") (pin "37") (pinfunction "PB3_37") (pintype "bidirectional"))
    )
    (net (code "77") (name "unconnected-(IC1B-PB4-Pad38)") (class "Default")
      (node (ref "IC1") (pin "38") (pinfunction "PB4_38") (pintype "bidirectional"))
    )
    (net (code "78") (name "unconnected-(IC1B-PB5-Pad39)") (class "Default")
      (node (ref "IC1") (pin "39") (pinfunction "PB5_39") (pintype "bidirectional"))
    )
    (net (code "79") (name "unconnected-(IC1B-PB6-Pad40)") (class "Default")
      (node (ref "IC1") (pin "40") (pinfunction "PB6_40") (pintype "bidirectional"))
    )
    (net (code "80") (name "unconnected-(IC1B-PB7-Pad41)") (class "Default")
      (node (ref "IC1") (pin "41") (pinfunction "PB7_41") (pintype "bidirectional"))
    )
    (net (code "81") (name "unconnected-(IC1D-PD5-Pad51)") (class "Default")
      (node (ref "IC1") (pin "51") (pinfunction "PD5_51") (pintype "bidirectional"))
    )
    (net (code "82") (name "unconnected-(IC1E-PE4-Pad17)") (class "Default")
      (node (ref "IC1") (pin "17") (pinfunction "PE4_17") (pintype "bidirectional"))
    )
    (net (code "83") (name "unconnected-(IC1G-PG2-Pad25)") (class "Default")
      (node (ref "IC1") (pin "25") (pinfunction "PG2_25") (pintype "bidirectional"))
    )
    (net (code "84") (name "unconnected-(IC1G-PG3-Pad48)") (class "Default")
      (node (ref "IC1") (pin "48") (pinfunction "PG3_48") (pintype "bidirectional"))
    )
    (net (code "85") (name "unconnected-(JP1-Pad3)") (class "Default")
      (node (ref "JP1") (pin "3") (pinfunction "3_3") (pintype "passive"))
    )
    (net (code "86") (name "unconnected-(JP1-Pad5)") (class "Default")
      (node (ref "JP1") (pin "5") (pinfunction "5_5") (pintype "passive"))
    )
    (net (code "87") (name "unconnected-(JP5-Pad2)") (class "Default")
      (node (ref "JP5") (pin "2") (pinfunction "2_2") (pintype "passive"))
    )
    (net (code "88") (name "unconnected-(JP5-Pad6)") (class "Default")
      (node (ref "JP5") (pin "6") (pinfunction "6_6") (pintype "passive"))
    )
    (net (code "89") (name "unconnected-(JP5-Pad8)") (class "Default")
      (node (ref "JP5") (pin "8") (pinfunction "8_8") (pintype "passive"))
    )
    (net (code "90") (name "unconnected-(T1-PadA2)") (class "Default")
      (node (ref "T1") (pin "A2") (pinfunction "A2_A2") (pintype "bidirectional"))
    )
    (net (code "91") (name "unconnected-(T1-PadB1)") (class "Default")
      (node (ref "T1") (pin "B1") (pinfunction "B1_B1") (pintype "bidirectional"))
    )
    (net (code "92") (name "unconnected-(T2-PadA2)") (class "Default")
      (node (ref "T2") (pin "A2") (pinfunction "A2_A2") (pintype "bidirectional"))
    )
    (net (code "93") (name "unconnected-(T2-PadB1)") (class "Default")
      (node (ref "T2") (pin "B1") (pinfunction "B1_B1") (pintype "bidirectional"))
    )
    (net (code "94") (name "unconnected-(T3-PadA2)") (class "Default")
      (node (ref "T3") (pin "A2") (pinfunction "A2_A2") (pintype "bidirectional"))
    )
    (net (code "95") (name "unconnected-(T3-PadB1)") (class "Default")
      (node (ref "T3") (pin "B1") (pinfunction "B1_B1") (pintype "bidirectional"))
    )
    (net (code "96") (name "unconnected-(T4-PadA2)") (class "Default")
      (node (ref "T4") (pin "A2") (pinfunction "A2_A2") (pintype "bidirectional"))
    )
    (net (code "97") (name "unconnected-(T4-PadB1)") (class "Default")
      (node (ref "T4") (pin "B1") (pinfunction "B1_B1") (pintype "bidirectional"))
    )
    (net (code "98") (name "unconnected-(T5-PadA2)") (class "Default")
      (node (ref "T5") (pin "A2") (pinfunction "A2_A2") (pintype "bidirectional"))
    )
    (net (code "99") (name "unconnected-(T5-PadB1)") (class "Default")
      (node (ref "T5") (pin "B1") (pinfunction "B1_B1") (pintype "bidirectional"))
    )
    (net (code "100") (name "unconnected-(T6-PadA2)") (class "Default")
      (node (ref "T6") (pin "A2") (pinfunction "A2_A2") (pintype "bidirectional"))
    )
    (net (code "101") (name "unconnected-(T6-PadB1)") (class "Default")
      (node (ref "T6") (pin "B1") (pinfunction "B1_B1") (pintype "bidirectional"))
    )
    (net (code "102") (name "unconnected-(T7-PadA2)") (class "Default")
      (node (ref "T7") (pin "A2") (pinfunction "A2_A2") (pintype "bidirectional"))
    )
    (net (code "103") (name "unconnected-(T7-PadB1)") (class "Default")
      (node (ref "T7") (pin "B1") (pinfunction "B1_B1") (pintype "bidirectional"))
    )
    (net (code "104") (name "unconnected-(T8-PadA2)") (class "Default")
      (node (ref "T8") (pin "A2") (pinfunction "A2_A2") (pintype "bidirectional"))
    )
    (net (code "105") (name "unconnected-(T8-PadB1)") (class "Default")
      (node (ref "T8") (pin "B1") (pinfunction "B1_B1") (pintype "bidirectional"))
    )
    (net (code "106") (name "unconnected-(T10-PadA2)") (class "Default")
      (node (ref "T10") (pin "A2") (pinfunction "A2_A2") (pintype "bidirectional"))
    )
    (net (code "107") (name "unconnected-(T10-PadB1)") (class "Default")
      (node (ref "T10") (pin "B1") (pinfunction "B1_B1") (pintype "bidirectional"))
    )
    (net (code "108") (name "unconnected-(T11-PadA2)") (class "Default")
      (node (ref "T11") (pin "A2") (pinfunction "A2_A2") (pintype "bidirectional"))
    )
    (net (code "109") (name "unconnected-(T11-PadB1)") (class "Default")
      (node (ref "T11") (pin "B1") (pinfunction "B1_B1") (pintype "bidirectional"))
    )
    (net (code "110") (name "unconnected-(T12-PadA2)") (class "Default")
      (node (ref "T12") (pin "A2") (pinfunction "A2_A2") (pintype "bidirectional"))
    )
    (net (code "111") (name "unconnected-(T12-PadB1)") (class "Default")
      (node (ref "T12") (pin "B1") (pinfunction "B1_B1") (pintype "bidirectional"))
    )
    (net (code "112") (name "unconnected-(T13-PadA2)") (class "Default")
      (node (ref "T13") (pin "A2") (pinfunction "A2_A2") (pintype "bidirectional"))
    )
    (net (code "113") (name "unconnected-(T13-PadB1)") (class "Default")
      (node (ref "T13") (pin "B1") (pinfunction "B1_B1") (pintype "bidirectional"))
    )
    (net (code "114") (name "unconnected-(T14-PadA2)") (class "Default")
      (node (ref "T14") (pin "A2") (pinfunction "A2_A2") (pintype "bidirectional"))
    )
    (net (code "115") (name "unconnected-(T14-PadB1)") (class "Default")
      (node (ref "T14") (pin "B1") (pinfunction "B1_B1") (pintype "bidirectional"))
    )
  )
)
